# part_2.net
KiCad netlist of a schematic drawn in Altium Designer
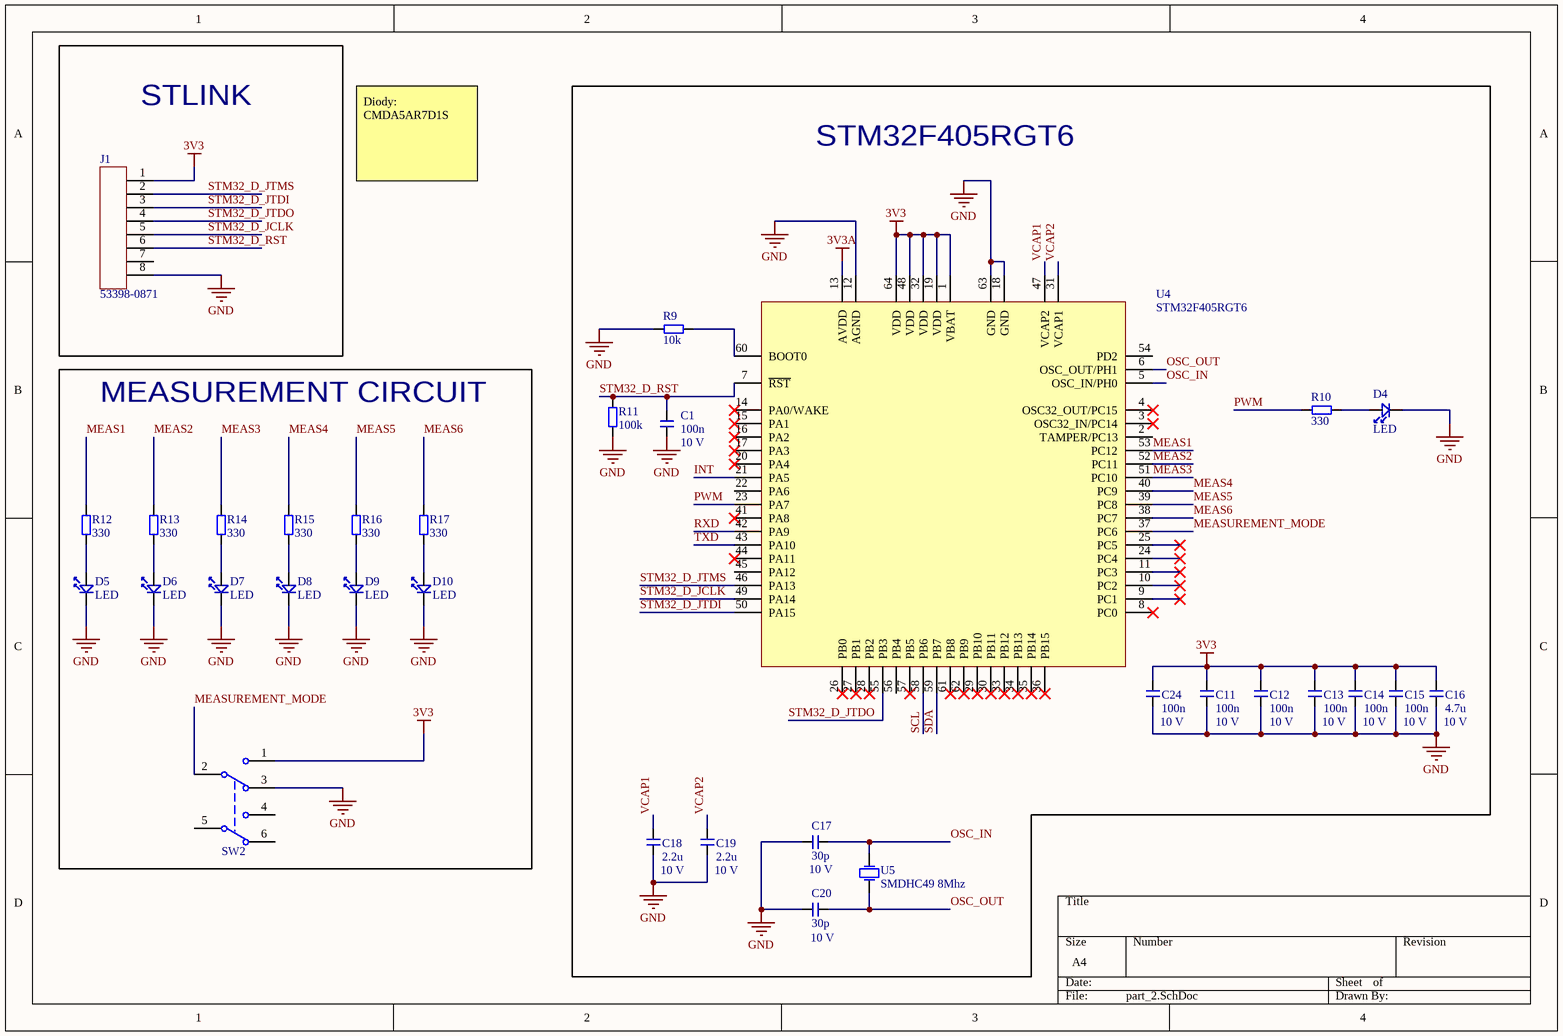
[diagram p0: part_2.SchDoc]

(export (version "E")
  (design (tool "Eeschema 10.0.6"))
  (components
    (comp (ref "C1")
      (value "100n")
      (footprint "0603")
      (description "kondensator ceramiczny")
      (fields (field (name "V") "10 V"))
      (libsource (lib "ETR-rozne") (part "CapN"))
    )
    (comp (ref "C11")
      (value "100n")
      (footprint "0603")
      (description "kondensator ceramiczny")
      (fields (field (name "V") "10 V"))
      (libsource (lib "ETR-rozne") (part "CapN"))
    )
    (comp (ref "C12")
      (value "100n")
      (footprint "0603")
      (description "kondensator ceramiczny")
      (fields (field (name "V") "10 V"))
      (libsource (lib "ETR-rozne") (part "CapN"))
    )
    (comp (ref "C13")
      (value "100n")
      (footprint "0603")
      (description "kondensator ceramiczny")
      (fields (field (name "V") "10 V"))
      (libsource (lib "ETR-rozne") (part "CapN"))
    )
    (comp (ref "C14")
      (value "100n")
      (footprint "0603")
      (description "kondensator ceramiczny")
      (fields (field (name "V") "10 V"))
      (libsource (lib "ETR-rozne") (part "CapN"))
    )
    (comp (ref "C15")
      (value "100n")
      (footprint "0603")
      (description "kondensator ceramiczny")
      (fields (field (name "V") "10 V"))
      (libsource (lib "ETR-rozne") (part "CapN"))
    )
    (comp (ref "C16")
      (value "4.7u")
      (footprint "0603")
      (description "kondensator ceramiczny")
      (fields (field (name "V") "10 V"))
      (libsource (lib "ETR-rozne") (part "CapN"))
    )
    (comp (ref "C17")
      (value "30p")
      (footprint "0603")
      (description "kondensator ceramiczny")
      (fields (field (name "V") "10 V"))
      (libsource (lib "ETR-rozne") (part "CapN"))
    )
    (comp (ref "C18")
      (value "2.2u")
      (footprint "0603")
      (description "kondensator ceramiczny")
      (fields (field (name "V") "10 V"))
      (libsource (lib "ETR-rozne") (part "CapN"))
    )
    (comp (ref "C19")
      (value "2.2u")
      (footprint "0603")
      (description "kondensator ceramiczny")
      (fields (field (name "V") "10 V"))
      (libsource (lib "ETR-rozne") (part "CapN"))
    )
    (comp (ref "C20")
      (value "30p")
      (footprint "0603")
      (description "kondensator ceramiczny")
      (fields (field (name "V") "10 V"))
      (libsource (lib "ETR-rozne") (part "CapN"))
    )
    (comp (ref "C24")
      (value "100n")
      (footprint "0603")
      (description "kondensator ceramiczny")
      (fields (field (name "V") "10 V"))
      (libsource (lib "ETR-rozne") (part "CapN"))
    )
    (comp (ref "D4")
      (value "LED")
      (footprint "Dioda_0805")
      (description "Dioda LED SMD")
      (libsource (lib "ETR-rozne") (part "Dioda_LED"))
    )
    (comp (ref "D5")
      (value "LED")
      (footprint "Dioda_0805")
      (description "Dioda LED SMD")
      (libsource (lib "ETR-rozne") (part "Dioda_LED"))
    )
    (comp (ref "D6")
      (value "LED")
      (footprint "Dioda_0805")
      (description "Dioda LED SMD")
      (libsource (lib "ETR-rozne") (part "Dioda_LED"))
    )
    (comp (ref "D7")
      (value "LED")
      (footprint "Dioda_0805")
      (description "Dioda LED SMD")
      (libsource (lib "ETR-rozne") (part "Dioda_LED"))
    )
    (comp (ref "D8")
      (value "LED")
      (footprint "Dioda_0805")
      (description "Dioda LED SMD")
      (libsource (lib "ETR-rozne") (part "Dioda_LED"))
    )
    (comp (ref "D9")
      (value "LED")
      (footprint "Dioda_0805")
      (description "Dioda LED SMD")
      (libsource (lib "ETR-rozne") (part "Dioda_LED"))
    )
    (comp (ref "D10")
      (value "LED")
      (footprint "Dioda_0805")
      (description "Dioda LED SMD")
      (libsource (lib "ETR-rozne") (part "Dioda_LED"))
    )
    (comp (ref "J1")
      (value "53398-0871")
      (footprint "Molex - PicoBlade:53398-0871")
      (description "Molex PicoBlade 8pin")
      (libsource (lib "Molex - PicoBlade") (part "CON8"))
    )
    (comp (ref "R9")
      (value "10k")
      (footprint "0603")
      (description "Rezystor SMD")
      (libsource (lib "ETR-rozne") (part "Res"))
    )
    (comp (ref "R10")
      (value "330")
      (footprint "0603")
      (description "Rezystor SMD")
      (libsource (lib "ETR-rozne") (part "Res"))
    )
    (comp (ref "R11")
      (value "100k")
      (footprint "0603")
      (description "Rezystor SMD")
      (libsource (lib "ETR-rozne") (part "Res"))
    )
    (comp (ref "R12")
      (value "330")
      (footprint "0603")
      (description "Rezystor SMD")
      (libsource (lib "ETR-rozne") (part "Res"))
    )
    (comp (ref "R13")
      (value "330")
      (footprint "0603")
      (description "Rezystor SMD")
      (libsource (lib "ETR-rozne") (part "Res"))
    )
    (comp (ref "R14")
      (value "330")
      (footprint "0603")
      (description "Rezystor SMD")
      (libsource (lib "ETR-rozne") (part "Res"))
    )
    (comp (ref "R15")
      (value "330")
      (footprint "0603")
      (description "Rezystor SMD")
      (libsource (lib "ETR-rozne") (part "Res"))
    )
    (comp (ref "R16")
      (value "330")
      (footprint "0603")
      (description "Rezystor SMD")
      (libsource (lib "ETR-rozne") (part "Res"))
    )
    (comp (ref "R17")
      (value "330")
      (footprint "0603")
      (description "Rezystor SMD")
      (libsource (lib "ETR-rozne") (part "Res"))
    )
    (comp (ref "SW2")
      (value "452403012014")
      (footprint "452403012014")
      (description "WS-SLSV SMT Mini Slide Switch, Same Side Connection, DPDT, 6VDC, 300mA, 350g")
      (fields (field (name "MANUFACTURER") "Wurth Elektronik"))
      (libsource (lib "Altium_WS-SLSV (rev24a)") (part "452403012014"))
    )
    (comp (ref "U4")
      (value "STM32F405RGT6")
      (footprint "LQFP 64 0.5")
      (description "STM32F415, 64 leads, LQFP")
      (libsource (lib "ETR-rozne") (part "STM32F415RGT6"))
    )
    (comp (ref "U5")
      (value "SMDHC49 8Mhz")
      (footprint "SMDHC_49")
      (description "rezonator kwarcowy")
      (libsource (lib "ETR-rozne") (part "kwarc"))
    )
  )
  (nets
    (net (code "1") (name "/INT") (class "Default")
      (node (ref "U4") (pin "21") (pinfunction "PA5_21") (pintype "passive"))
    )
    (net (code "2") (name "/MEAS1") (class "Default")
      (node (ref "R12") (pin "2") (pinfunction "2_2") (pintype "passive"))
      (node (ref "U4") (pin "53") (pinfunction "PC12_53") (pintype "passive"))
    )
    (net (code "3") (name "/MEAS2") (class "Default")
      (node (ref "R13") (pin "2") (pinfunction "2_2") (pintype "passive"))
      (node (ref "U4") (pin "52") (pinfunction "PC11_52") (pintype "passive"))
    )
    (net (code "4") (name "/MEAS3") (class "Default")
      (node (ref "R14") (pin "2") (pinfunction "2_2") (pintype "passive"))
      (node (ref "U4") (pin "51") (pinfunction "PC10_51") (pintype "passive"))
    )
    (net (code "5") (name "/MEAS4") (class "Default")
      (node (ref "R15") (pin "2") (pinfunction "2_2") (pintype "passive"))
      (node (ref "U4") (pin "40") (pinfunction "PC9_40") (pintype "passive"))
    )
    (net (code "6") (name "/MEAS5") (class "Default")
      (node (ref "R16") (pin "2") (pinfunction "2_2") (pintype "passive"))
      (node (ref "U4") (pin "39") (pinfunction "PC8_39") (pintype "passive"))
    )
    (net (code "7") (name "/MEAS6") (class "Default")
      (node (ref "R17") (pin "2") (pinfunction "2_2") (pintype "passive"))
      (node (ref "U4") (pin "38") (pinfunction "PC7_38") (pintype "passive"))
    )
    (net (code "8") (name "/MEASUREMENT_MODE") (class "Default")
      (node (ref "SW2") (pin "2") (pinfunction "COM_2") (pintype "passive"))
      (node (ref "U4") (pin "37") (pinfunction "PC6_37") (pintype "passive"))
    )
    (net (code "9") (name "/OSC_IN") (class "Default")
      (node (ref "C17") (pin "1") (pinfunction "1_1") (pintype "passive"))
      (node (ref "U4") (pin "5") (pinfunction "OSC_IN/PH0_5") (pintype "passive"))
      (node (ref "U5") (pin "2") (pinfunction "OSC2_2") (pintype "passive"))
    )
    (net (code "10") (name "/OSC_OUT") (class "Default")
      (node (ref "C20") (pin "1") (pinfunction "1_1") (pintype "passive"))
      (node (ref "U4") (pin "6") (pinfunction "OSC_OUT/PH1_6") (pintype "passive"))
      (node (ref "U5") (pin "1") (pinfunction "OSC1_1") (pintype "passive"))
    )
    (net (code "11") (name "/PWM") (class "Default")
      (node (ref "R10") (pin "1") (pinfunction "1_1") (pintype "passive"))
      (node (ref "U4") (pin "23") (pinfunction "PA7_23") (pintype "passive"))
    )
    (net (code "12") (name "/RXD") (class "Default")
      (node (ref "U4") (pin "42") (pinfunction "PA9_42") (pintype "passive"))
    )
    (net (code "13") (name "/SCL") (class "Default")
      (node (ref "U4") (pin "58") (pinfunction "PB6_58") (pintype "passive"))
    )
    (net (code "14") (name "/SDA") (class "Default")
      (node (ref "U4") (pin "59") (pinfunction "PB7_59") (pintype "passive"))
    )
    (net (code "15") (name "/STM32_D_JCLK") (class "Default")
      (node (ref "J1") (pin "5") (pinfunction "5_5") (pintype "passive"))
      (node (ref "U4") (pin "49") (pinfunction "PA14_49") (pintype "passive"))
    )
    (net (code "16") (name "/STM32_D_JTDI") (class "Default")
      (node (ref "J1") (pin "3") (pinfunction "3_3") (pintype "passive"))
      (node (ref "U4") (pin "50") (pinfunction "PA15_50") (pintype "passive"))
    )
    (net (code "17") (name "/STM32_D_JTDO") (class "Default")
      (node (ref "J1") (pin "4") (pinfunction "4_4") (pintype "passive"))
      (node (ref "U4") (pin "55") (pinfunction "PB3_55") (pintype "passive"))
    )
    (net (code "18") (name "/STM32_D_JTMS") (class "Default")
      (node (ref "J1") (pin "2") (pinfunction "2_2") (pintype "passive"))
      (node (ref "U4") (pin "46") (pinfunction "PA13_46") (pintype "passive"))
    )
    (net (code "19") (name "/STM32_D_RST") (class "Default")
      (node (ref "C1") (pin "2") (pinfunction "2_2") (pintype "passive"))
      (node (ref "J1") (pin "6") (pinfunction "6_6") (pintype "passive"))
      (node (ref "R11") (pin "2") (pinfunction "2_2") (pintype "passive"))
      (node (ref "U4") (pin "7") (pinfunction "~{RST}_7") (pintype "passive"))
    )
    (net (code "20") (name "/TXD") (class "Default")
      (node (ref "U4") (pin "43") (pinfunction "PA10_43") (pintype "passive"))
    )
    (net (code "21") (name "/VCAP1") (class "Default")
      (node (ref "C18") (pin "2") (pinfunction "2_2") (pintype "passive"))
      (node (ref "U4") (pin "47") (pinfunction "VCAP2_47") (pintype "passive"))
    )
    (net (code "22") (name "/VCAP2") (class "Default")
      (node (ref "C19") (pin "2") (pinfunction "2_2") (pintype "passive"))
      (node (ref "U4") (pin "31") (pinfunction "VCAP1_31") (pintype "passive"))
    )
    (net (code "23") (name "3V3") (class "Default")
      (node (ref "C11") (pin "2") (pinfunction "2_2") (pintype "passive"))
      (node (ref "C12") (pin "2") (pinfunction "2_2") (pintype "passive"))
      (node (ref "C13") (pin "2") (pinfunction "2_2") (pintype "passive"))
      (node (ref "C14") (pin "2") (pinfunction "2_2") (pintype "passive"))
      (node (ref "C15") (pin "2") (pinfunction "2_2") (pintype "passive"))
      (node (ref "C16") (pin "2") (pinfunction "2_2") (pintype "passive"))
      (node (ref "C24") (pin "2") (pinfunction "2_2") (pintype "passive"))
      (node (ref "J1") (pin "1") (pinfunction "1_1") (pintype "passive"))
      (node (ref "SW2") (pin "1") (pinfunction "1_1") (pintype "passive"))
      (node (ref "U4") (pin "1") (pinfunction "VBAT_1") (pintype "passive"))
      (node (ref "U4") (pin "19") (pinfunction "VDD_19") (pintype "passive"))
      (node (ref "U4") (pin "32") (pinfunction "VDD_32") (pintype "passive"))
      (node (ref "U4") (pin "48") (pinfunction "VDD_48") (pintype "passive"))
      (node (ref "U4") (pin "64") (pinfunction "VDD_64") (pintype "passive"))
    )
    (net (code "24") (name "3V3A") (class "Default")
      (node (ref "U4") (pin "13") (pinfunction "AVDD_13") (pintype "passive"))
    )
    (net (code "25") (name "GND") (class "Default")
      (node (ref "C1") (pin "1") (pinfunction "1_1") (pintype "passive"))
      (node (ref "C11") (pin "1") (pinfunction "1_1") (pintype "passive"))
      (node (ref "C12") (pin "1") (pinfunction "1_1") (pintype "passive"))
      (node (ref "C13") (pin "1") (pinfunction "1_1") (pintype "passive"))
      (node (ref "C14") (pin "1") (pinfunction "1_1") (pintype "passive"))
      (node (ref "C15") (pin "1") (pinfunction "1_1") (pintype "passive"))
      (node (ref "C16") (pin "1") (pinfunction "1_1") (pintype "passive"))
      (node (ref "C17") (pin "2") (pinfunction "2_2") (pintype "passive"))
      (node (ref "C18") (pin "1") (pinfunction "1_1") (pintype "passive"))
      (node (ref "C19") (pin "1") (pinfunction "1_1") (pintype "passive"))
      (node (ref "C20") (pin "2") (pinfunction "2_2") (pintype "passive"))
      (node (ref "C24") (pin "1") (pinfunction "1_1") (pintype "passive"))
      (node (ref "D10") (pin "1") (pinfunction "1_1") (pintype "passive"))
      (node (ref "D4") (pin "1") (pinfunction "1_1") (pintype "passive"))
      (node (ref "D5") (pin "1") (pinfunction "1_1") (pintype "passive"))
      (node (ref "D6") (pin "1") (pinfunction "1_1") (pintype "passive"))
      (node (ref "D7") (pin "1") (pinfunction "1_1") (pintype "passive"))
      (node (ref "D8") (pin "1") (pinfunction "1_1") (pintype "passive"))
      (node (ref "D9") (pin "1") (pinfunction "1_1") (pintype "passive"))
      (node (ref "J1") (pin "8") (pinfunction "8_8") (pintype "passive"))
      (node (ref "R11") (pin "1") (pinfunction "1_1") (pintype "passive"))
      (node (ref "R9") (pin "1") (pinfunction "1_1") (pintype "passive"))
      (node (ref "SW2") (pin "3") (pinfunction "3_3") (pintype "passive"))
      (node (ref "U4") (pin "12") (pinfunction "AGND_12") (pintype "passive"))
      (node (ref "U4") (pin "18") (pinfunction "GND_18") (pintype "passive"))
      (node (ref "U4") (pin "63") (pinfunction "GND_63") (pintype "passive"))
    )
    (net (code "26") (name "Net-(D4-Pad2)") (class "Default")
      (node (ref "D4") (pin "2") (pinfunction "2_2") (pintype "passive"))
      (node (ref "R10") (pin "2") (pinfunction "2_2") (pintype "passive"))
    )
    (net (code "27") (name "Net-(D5-Pad2)") (class "Default")
      (node (ref "D5") (pin "2") (pinfunction "2_2") (pintype "passive"))
      (node (ref "R12") (pin "1") (pinfunction "1_1") (pintype "passive"))
    )
    (net (code "28") (name "Net-(D6-Pad2)") (class "Default")
      (node (ref "D6") (pin "2") (pinfunction "2_2") (pintype "passive"))
      (node (ref "R13") (pin "1") (pinfunction "1_1") (pintype "passive"))
    )
    (net (code "29") (name "Net-(D7-Pad2)") (class "Default")
      (node (ref "D7") (pin "2") (pinfunction "2_2") (pintype "passive"))
      (node (ref "R14") (pin "1") (pinfunction "1_1") (pintype "passive"))
    )
    (net (code "30") (name "Net-(D8-Pad2)") (class "Default")
      (node (ref "D8") (pin "2") (pinfunction "2_2") (pintype "passive"))
      (node (ref "R15") (pin "1") (pinfunction "1_1") (pintype "passive"))
    )
    (net (code "31") (name "Net-(D9-Pad2)") (class "Default")
      (node (ref "D9") (pin "2") (pinfunction "2_2") (pintype "passive"))
      (node (ref "R16") (pin "1") (pinfunction "1_1") (pintype "passive"))
    )
    (net (code "32") (name "Net-(D10-Pad2)") (class "Default")
      (node (ref "D10") (pin "2") (pinfunction "2_2") (pintype "passive"))
      (node (ref "R17") (pin "1") (pinfunction "1_1") (pintype "passive"))
    )
    (net (code "33") (name "Net-(U4-BOOT0)") (class "Default")
      (node (ref "R9") (pin "2") (pinfunction "2_2") (pintype "passive"))
      (node (ref "U4") (pin "60") (pinfunction "BOOT0_60") (pintype "passive"))
    )
    (net (code "34") (name "unconnected-(J1-Pad7)") (class "Default")
      (node (ref "J1") (pin "7") (pinfunction "7_7") (pintype "passive"))
    )
    (net (code "35") (name "unconnected-(SW2-COM-Pad5)") (class "Default")
      (node (ref "SW2") (pin "5") (pinfunction "COM_5") (pintype "passive"))
    )
    (net (code "36") (name "unconnected-(SW2-Pad4)") (class "Default")
      (node (ref "SW2") (pin "4") (pinfunction "4_4") (pintype "passive"))
    )
    (net (code "37") (name "unconnected-(SW2-Pad6)") (class "Default")
      (node (ref "SW2") (pin "6") (pinfunction "6_6") (pintype "passive"))
    )
    (net (code "38") (name "unconnected-(U4-OSC32_IN{slash}PC14-Pad3)") (class "Default")
      (node (ref "U4") (pin "3") (pinfunction "OSC32_IN/PC14_3") (pintype "passive+no_connect"))
    )
    (net (code "39") (name "unconnected-(U4-OSC32_OUT{slash}PC15-Pad4)") (class "Default")
      (node (ref "U4") (pin "4") (pinfunction "OSC32_OUT/PC15_4") (pintype "passive+no_connect"))
    )
    (net (code "40") (name "unconnected-(U4-PA0{slash}WAKE-Pad14)") (class "Default")
      (node (ref "U4") (pin "14") (pinfunction "PA0/WAKE_14") (pintype "passive+no_connect"))
    )
    (net (code "41") (name "unconnected-(U4-PA1-Pad15)") (class "Default")
      (node (ref "U4") (pin "15") (pinfunction "PA1_15") (pintype "passive+no_connect"))
    )
    (net (code "42") (name "unconnected-(U4-PA2-Pad16)") (class "Default")
      (node (ref "U4") (pin "16") (pinfunction "PA2_16") (pintype "passive+no_connect"))
    )
    (net (code "43") (name "unconnected-(U4-PA3-Pad17)") (class "Default")
      (node (ref "U4") (pin "17") (pinfunction "PA3_17") (pintype "passive+no_connect"))
    )
    (net (code "44") (name "unconnected-(U4-PA4-Pad20)") (class "Default")
      (node (ref "U4") (pin "20") (pinfunction "PA4_20") (pintype "passive+no_connect"))
    )
    (net (code "45") (name "unconnected-(U4-PA6-Pad22)") (class "Default")
      (node (ref "U4") (pin "22") (pinfunction "PA6_22") (pintype "passive"))
    )
    (net (code "46") (name "unconnected-(U4-PA8-Pad41)") (class "Default")
      (node (ref "U4") (pin "41") (pinfunction "PA8_41") (pintype "passive+no_connect"))
    )
    (net (code "47") (name "unconnected-(U4-PA11-Pad44)") (class "Default")
      (node (ref "U4") (pin "44") (pinfunction "PA11_44") (pintype "passive+no_connect"))
    )
    (net (code "48") (name "unconnected-(U4-PA12-Pad45)") (class "Default")
      (node (ref "U4") (pin "45") (pinfunction "PA12_45") (pintype "passive"))
    )
    (net (code "49") (name "unconnected-(U4-PB0-Pad26)") (class "Default")
      (node (ref "U4") (pin "26") (pinfunction "PB0_26") (pintype "passive+no_connect"))
    )
    (net (code "50") (name "unconnected-(U4-PB1-Pad27)") (class "Default")
      (node (ref "U4") (pin "27") (pinfunction "PB1_27") (pintype "passive+no_connect"))
    )
    (net (code "51") (name "unconnected-(U4-PB2-Pad28)") (class "Default")
      (node (ref "U4") (pin "28") (pinfunction "PB2_28") (pintype "passive+no_connect"))
    )
    (net (code "52") (name "unconnected-(U4-PB4-Pad56)") (class "Default")
      (node (ref "U4") (pin "56") (pinfunction "PB4_56") (pintype "passive"))
    )
    (net (code "53") (name "unconnected-(U4-PB5-Pad57)") (class "Default")
      (node (ref "U4") (pin "57") (pinfunction "PB5_57") (pintype "passive+no_connect"))
    )
    (net (code "54") (name "unconnected-(U4-PB8-Pad61)") (class "Default")
      (node (ref "U4") (pin "61") (pinfunction "PB8_61") (pintype "passive+no_connect"))
    )
    (net (code "55") (name "unconnected-(U4-PB9-Pad62)") (class "Default")
      (node (ref "U4") (pin "62") (pinfunction "PB9_62") (pintype "passive+no_connect"))
    )
    (net (code "56") (name "unconnected-(U4-PB10-Pad29)") (class "Default")
      (node (ref "U4") (pin "29") (pinfunction "PB10_29") (pintype "passive+no_connect"))
    )
    (net (code "57") (name "unconnected-(U4-PB11-Pad30)") (class "Default")
      (node (ref "U4") (pin "30") (pinfunction "PB11_30") (pintype "passive+no_connect"))
    )
    (net (code "58") (name "unconnected-(U4-PB12-Pad33)") (class "Default")
      (node (ref "U4") (pin "33") (pinfunction "PB12_33") (pintype "passive+no_connect"))
    )
    (net (code "59") (name "unconnected-(U4-PB13-Pad34)") (class "Default")
      (node (ref "U4") (pin "34") (pinfunction "PB13_34") (pintype "passive+no_connect"))
    )
    (net (code "60") (name "unconnected-(U4-PB14-Pad35)") (class "Default")
      (node (ref "U4") (pin "35") (pinfunction "PB14_35") (pintype "passive+no_connect"))
    )
    (net (code "61") (name "unconnected-(U4-PB15-Pad36)") (class "Default")
      (node (ref "U4") (pin "36") (pinfunction "PB15_36") (pintype "passive+no_connect"))
    )
    (net (code "62") (name "unconnected-(U4-PC0-Pad8)") (class "Default")
      (node (ref "U4") (pin "8") (pinfunction "PC0_8") (pintype "passive+no_connect"))
    )
    (net (code "63") (name "unconnected-(U4-PC1-Pad9)") (class "Default")
      (node (ref "U4") (pin "9") (pinfunction "PC1_9") (pintype "passive+no_connect"))
    )
    (net (code "64") (name "unconnected-(U4-PC2-Pad10)") (class "Default")
      (node (ref "U4") (pin "10") (pinfunction "PC2_10") (pintype "passive+no_connect"))
    )
    (net (code "65") (name "unconnected-(U4-PC3-Pad11)") (class "Default")
      (node (ref "U4") (pin "11") (pinfunction "PC3_11") (pintype "passive+no_connect"))
    )
    (net (code "66") (name "unconnected-(U4-PC4-Pad24)") (class "Default")
      (node (ref "U4") (pin "24") (pinfunction "PC4_24") (pintype "passive+no_connect"))
    )
    (net (code "67") (name "unconnected-(U4-PC5-Pad25)") (class "Default")
      (node (ref "U4") (pin "25") (pinfunction "PC5_25") (pintype "passive+no_connect"))
    )
    (net (code "68") (name "unconnected-(U4-PD2-Pad54)") (class "Default")
      (node (ref "U4") (pin "54") (pinfunction "PD2_54") (pintype "passive"))
    )
    (net (code "69") (name "unconnected-(U4-TAMPER{slash}PC13-Pad2)") (class "Default")
      (node (ref "U4") (pin "2") (pinfunction "TAMPER/PC13_2") (pintype "passive"))
    )
  )
)
